# PAGE1_-_MAIN.net
KiCad netlist of a schematic drawn in Altium Designer
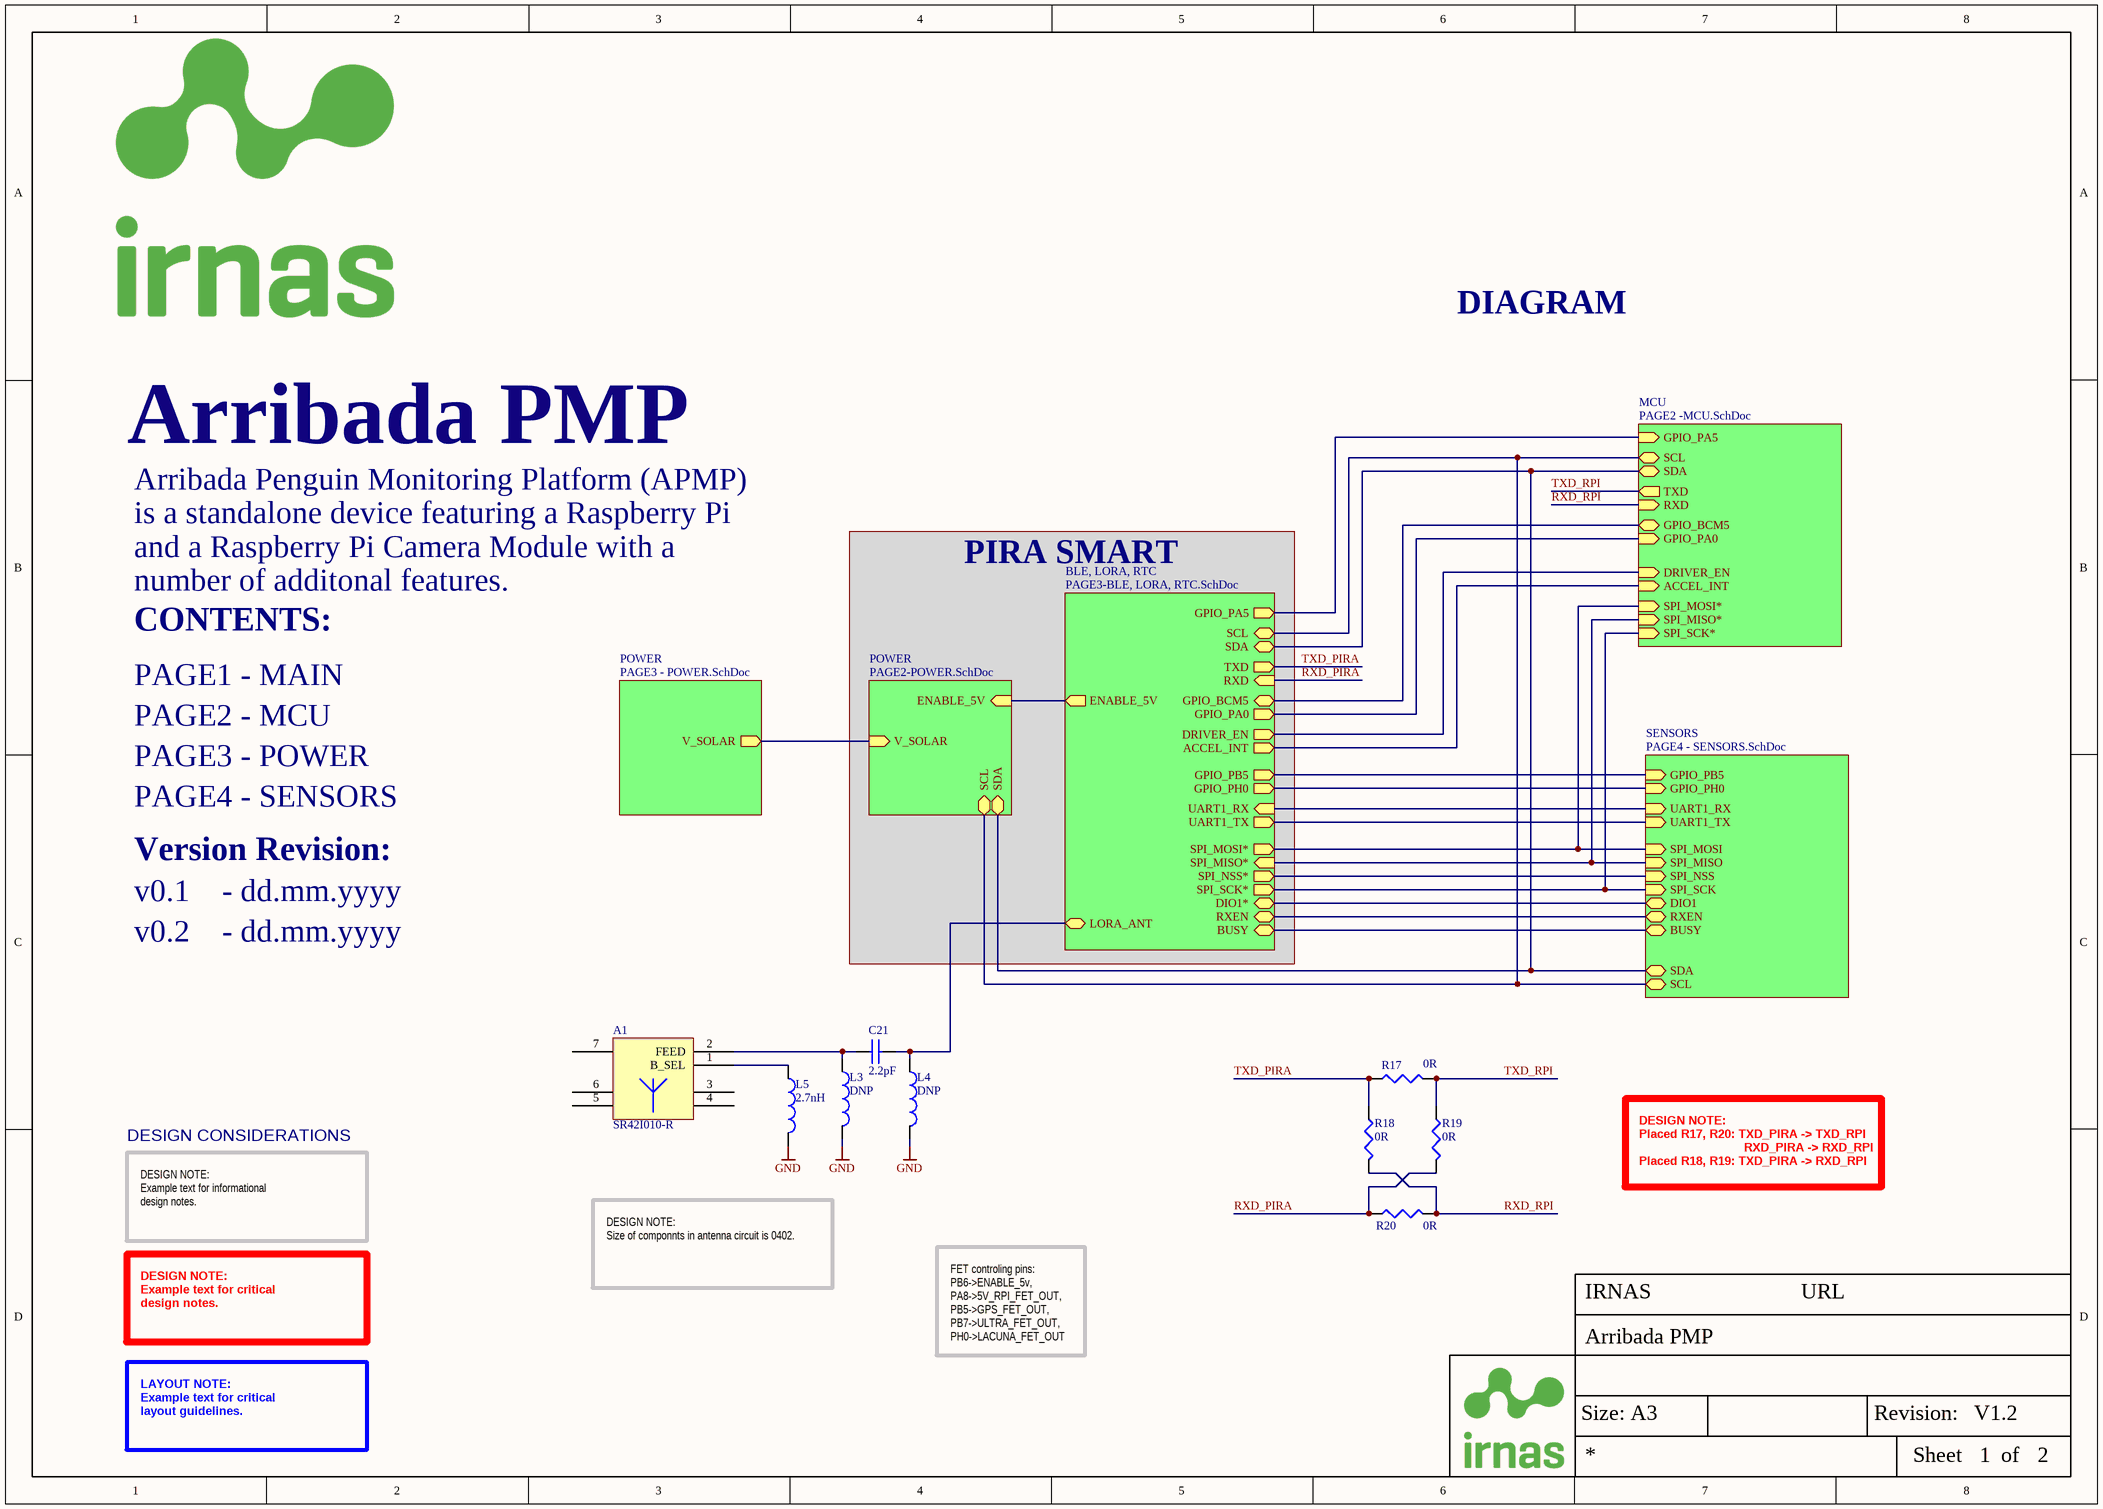
[diagram p0: PAGE1 - MAIN.SchDoc]

(export (version "E")
  (design (tool "Eeschema 10.0.6"))
  (components
    (comp (ref "A1")
      (value "SR42I010-R")
      (footprint "LORA_PCB_ANTENNA")
      (description "Antenna SMD -4dBi Gain 870MHz/928MHz Automotive 7-Pin SMD T/R")
      (fields (field (name "MANUFACTURER") "Antenova"))
      (libsource (lib "Passive") (part "ANT - SR42I010-R_1"))
    )
    (comp (ref "C21")
      (value "2.2pF")
      (footprint "CAP0402")
      (description "Multilayer Ceramic Capacitors MLCC - SMD/SMT 50volts 1.8pF C0G")
      (fields
        (field (name "MANUFACTURER") "KEMET")
        (field (name "MANUFACTURER PART NUMBER") "C0402C189B5GACTU")
      )
      (libsource (lib "Passive") (part "C - 1.8pF/0402"))
    )
    (comp (ref "L3")
      (value "DNP")
      (footprint "IND0402")
      (description "Inductor RF Chip Multi-Layer 4.3nH 0.3nH 100MHz 8Q-Factor Air 300mA 210mOhm DCR 0402 Paper T/R")
      (fields
        (field (name "MANUFACTURER") "Murata")
        (field (name "MANUFACTURER PART NUMBER") "LQG15HN4N3S02D")
      )
      (libsource (lib "Passive") (part "L - 4.3nH/0402"))
    )
    (comp (ref "L4")
      (value "DNP")
      (footprint "IND0402")
      (description "Inductor RF Chip Multi-Layer 4.3nH 0.3nH 100MHz 8Q-Factor Air 300mA 210mOhm DCR 0402 Paper T/R")
      (fields
        (field (name "MANUFACTURER") "Murata")
        (field (name "MANUFACTURER PART NUMBER") "LQG15HN4N3S02D")
      )
      (libsource (lib "Passive") (part "L - 4.3nH/0402"))
    )
    (comp (ref "L5")
      (value "2.7nH")
      (footprint "IND0402")
      (description "Inductor RF Chip Multi-Layer 4.3nH 0.3nH 100MHz 8Q-Factor Air 300mA 210mOhm DCR 0402 Paper T/R")
      (fields
        (field (name "MANUFACTURER") "Murata")
        (field (name "MANUFACTURER PART NUMBER") "LQG15HN4N3S02D")
      )
      (libsource (lib "Passive") (part "L - 4.3nH/0402"))
    )
    (comp (ref "R17")
      (value "0R")
      (footprint "RES0603")
      (description "BOURNS - CR0603-J/-000ELF - RES, THICK FILM, 0R, 5%, 0.1W, 0603")
      (fields
        (field (name "MANUFACTURER") "BOURNS")
        (field (name "MANUFACTURER PART NUMBER") "CR0603-J/-000ELF")
      )
      (libsource (lib "Passive") (part "R - 0R"))
    )
    (comp (ref "R18")
      (value "0R")
      (footprint "RES0603")
      (description "BOURNS - CR0603-J/-000ELF - RES, THICK FILM, 0R, 5%, 0.1W, 0603")
      (fields
        (field (name "MANUFACTURER") "BOURNS")
        (field (name "MANUFACTURER PART NUMBER") "CR0603-J/-000ELF")
      )
      (libsource (lib "Passive") (part "R - 0R"))
    )
    (comp (ref "R19")
      (value "0R")
      (footprint "RES0603")
      (description "BOURNS - CR0603-J/-000ELF - RES, THICK FILM, 0R, 5%, 0.1W, 0603")
      (fields
        (field (name "MANUFACTURER") "BOURNS")
        (field (name "MANUFACTURER PART NUMBER") "CR0603-J/-000ELF")
      )
      (libsource (lib "Passive") (part "R - 0R"))
    )
    (comp (ref "R20")
      (value "0R")
      (footprint "RES0603")
      (description "BOURNS - CR0603-J/-000ELF - RES, THICK FILM, 0R, 5%, 0.1W, 0603")
      (fields
        (field (name "MANUFACTURER") "BOURNS")
        (field (name "MANUFACTURER PART NUMBER") "CR0603-J/-000ELF")
      )
      (libsource (lib "Passive") (part "R - 0R"))
    )
  )
  (nets
    (net (code "11") (name "/LORA_ANT") (class "Default")
      (node (ref "C21") (pin "2") (pinfunction "2_2") (pintype "passive"))
      (node (ref "L4") (pin "2") (pinfunction "2_2") (pintype "passive"))
    )
    (net (code "12") (name "/RXD_PIRA") (class "Default")
      (node (ref "R19") (pin "2") (pinfunction "2_2") (pintype "passive"))
      (node (ref "R20") (pin "1") (pinfunction "1_1") (pintype "passive"))
    )
    (net (code "13") (name "/RXD_RPI") (class "Default")
      (node (ref "R18") (pin "2") (pinfunction "2_2") (pintype "passive"))
      (node (ref "R20") (pin "2") (pinfunction "2_2") (pintype "passive"))
    )
    (net (code "21") (name "/TXD_PIRA") (class "Default")
      (node (ref "R17") (pin "1") (pinfunction "1_1") (pintype "passive"))
      (node (ref "R18") (pin "1") (pinfunction "1_1") (pintype "passive"))
    )
    (net (code "22") (name "/TXD_RPI") (class "Default")
      (node (ref "R17") (pin "2") (pinfunction "2_2") (pintype "passive"))
      (node (ref "R19") (pin "1") (pinfunction "1_1") (pintype "passive"))
    )
    (net (code "26") (name "GND") (class "Default")
      (node (ref "L3") (pin "1") (pinfunction "1_1") (pintype "passive"))
      (node (ref "L4") (pin "1") (pinfunction "1_1") (pintype "passive"))
      (node (ref "L5") (pin "1") (pinfunction "1_1") (pintype "passive"))
    )
    (net (code "27") (name "Net-(A1-B_SEL)") (class "Default")
      (node (ref "A1") (pin "1") (pinfunction "B_SEL_1") (pintype "passive"))
      (node (ref "L5") (pin "2") (pinfunction "2_2") (pintype "passive"))
    )
    (net (code "28") (name "Net-(A1-FEED)") (class "Default")
      (node (ref "A1") (pin "2") (pinfunction "FEED_2") (pintype "passive"))
      (node (ref "C21") (pin "1") (pinfunction "1_1") (pintype "passive"))
      (node (ref "L3") (pin "2") (pinfunction "2_2") (pintype "passive"))
    )
    (net (code "29") (name "unconnected-(A1-Pad3)") (class "Default")
      (node (ref "A1") (pin "3") (pintype "passive"))
    )
    (net (code "30") (name "unconnected-(A1-Pad4)") (class "Default")
      (node (ref "A1") (pin "4") (pintype "passive"))
    )
    (net (code "31") (name "unconnected-(A1-Pad5)") (class "Default")
      (node (ref "A1") (pin "5") (pintype "passive"))
    )
    (net (code "32") (name "unconnected-(A1-Pad6)") (class "Default")
      (node (ref "A1") (pin "6") (pintype "passive"))
    )
    (net (code "33") (name "unconnected-(A1-Pad7)") (class "Default")
      (node (ref "A1") (pin "7") (pintype "passive"))
    )
  )
)
